# board1.net
KiCad netlist of a schematic drawn in EAGLE
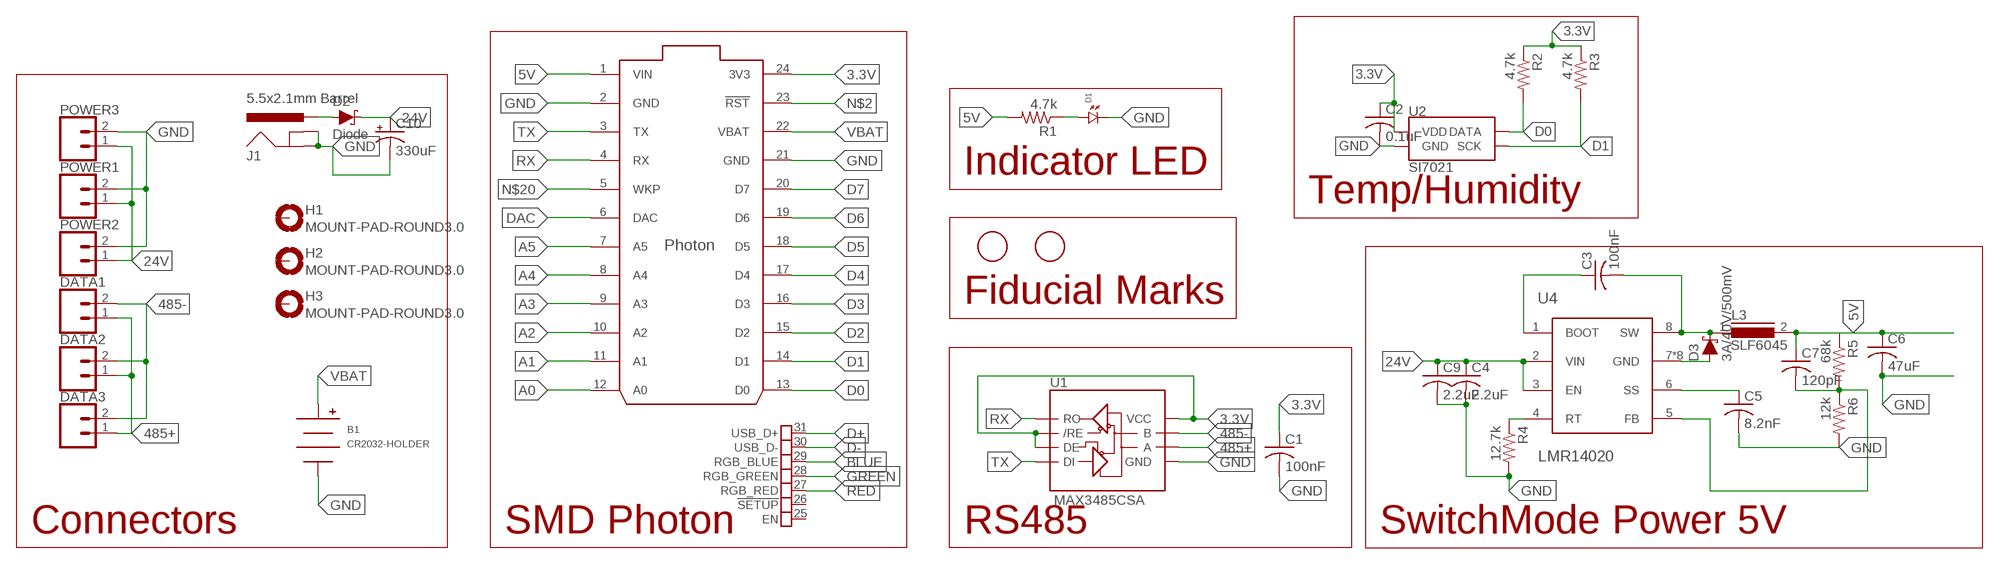
[diagram p0: schematic, sheet 1]

(export (version "E")
  (design (tool "Eeschema 10.0.6"))
  (components
    (comp (ref "B1")
      (value "CR2032-HOLDER")
      (footprint "eagle-import:CH28-2032LF")
      (libsource (lib "eagle-import") (part "CR2032-HOLDER"))
    )
    (comp (ref "C1")
      (value "100nF")
      (footprint "eagle-import:C0805")
      (libsource (lib "eagle-import") (part "C-USC0805"))
    )
    (comp (ref "C2")
      (value "0.1uF")
      (footprint "eagle-import:C0805")
      (libsource (lib "eagle-import") (part "C-USC0805"))
    )
    (comp (ref "C3")
      (value "100nF")
      (footprint "eagle-import:C0805")
      (libsource (lib "eagle-import") (part "C-USC0805"))
    )
    (comp (ref "C4")
      (value "2.2uF")
      (footprint "eagle-import:C0805")
      (libsource (lib "eagle-import") (part "C-USC0805"))
    )
    (comp (ref "C5")
      (value "8.2nF")
      (footprint "eagle-import:C0805")
      (libsource (lib "eagle-import") (part "C-USC0805"))
    )
    (comp (ref "C6")
      (value "47uF")
      (footprint "eagle-import:C0805")
      (libsource (lib "eagle-import") (part "C-USC0805"))
    )
    (comp (ref "C7")
      (value "120pF")
      (footprint "eagle-import:C0805")
      (libsource (lib "eagle-import") (part "C-USC0805"))
    )
    (comp (ref "C9")
      (value "2.2uF")
      (footprint "eagle-import:C0805")
      (libsource (lib "eagle-import") (part "C-USC0805"))
    )
    (comp (ref "C10")
      (value "330uF")
      (footprint "eagle-import:175TMP-0808")
      (libsource (lib "eagle-import") (part "CPOL-US175TMP-0808"))
    )
    (comp (ref "D1")
      (value "LED.0805")
      (footprint "eagle-import:0805.LED")
      (libsource (lib "eagle-import") (part "LED.0805"))
    )
    (comp (ref "D2")
      (value "Diode")
      (footprint "eagle-import:SMA-DIODE")
      (libsource (lib "eagle-import") (part "DIODE-SCHOTTKY-B340A"))
    )
    (comp (ref "D3")
      (value "3A/40V/500mV")
      (footprint "eagle-import:SMA-DIODE")
      (libsource (lib "eagle-import") (part "DIODE-SCHOTTKY-B340A"))
    )
    (comp (ref "DATA1")
      (value "CONN_025MM")
      (footprint "eagle-import:SCREWTERMINAL-5MM-2")
      (libsource (lib "eagle-import") (part "CONN_025MM"))
    )
    (comp (ref "DATA2")
      (value "CONN_025MM")
      (footprint "eagle-import:SCREWTERMINAL-5MM-2")
      (libsource (lib "eagle-import") (part "CONN_025MM"))
    )
    (comp (ref "DATA3")
      (value "CONN_025MM")
      (footprint "eagle-import:SCREWTERMINAL-5MM-2")
      (libsource (lib "eagle-import") (part "CONN_025MM"))
    )
    (comp (ref "FID1")
      (value "FIDUCIAL")
      (footprint "eagle-import:FIDUCIAL_1MM")
      (libsource (lib "eagle-import") (part "FIDUCIAL"))
    )
    (comp (ref "FID2")
      (value "FIDUCIAL")
      (footprint "eagle-import:FIDUCIAL_1MM")
      (libsource (lib "eagle-import") (part "FIDUCIAL"))
    )
    (comp (ref "H1")
      (value "MOUNT-PAD-ROUND3.0")
      (footprint "eagle-import:3,0-PAD")
      (libsource (lib "eagle-import") (part "MOUNT-PAD-ROUND3.0"))
    )
    (comp (ref "H2")
      (value "MOUNT-PAD-ROUND3.0")
      (footprint "eagle-import:3,0-PAD")
      (libsource (lib "eagle-import") (part "MOUNT-PAD-ROUND3.0"))
    )
    (comp (ref "H3")
      (value "MOUNT-PAD-ROUND3.0")
      (footprint "eagle-import:3,0-PAD")
      (libsource (lib "eagle-import") (part "MOUNT-PAD-ROUND3.0"))
    )
    (comp (ref "J1")
      (value "5.5x2.1mm Barrel")
      (footprint "eagle-import:POWER_JACK_SMD")
      (libsource (lib "eagle-import") (part "POWER_JACKSMD"))
    )
    (comp (ref "L3")
      (value "SLF6045")
      (footprint "eagle-import:SLF7045")
      (libsource (lib "eagle-import") (part "SLF7045"))
    )
    (comp (ref "POWER1")
      (value "CONN_025MM")
      (footprint "eagle-import:SCREWTERMINAL-5MM-2")
      (libsource (lib "eagle-import") (part "CONN_025MM"))
    )
    (comp (ref "POWER2")
      (value "CONN_025MM")
      (footprint "eagle-import:SCREWTERMINAL-5MM-2")
      (libsource (lib "eagle-import") (part "CONN_025MM"))
    )
    (comp (ref "POWER3")
      (value "CONN_025MM")
      (footprint "eagle-import:SCREWTERMINAL-5MM-2")
      (libsource (lib "eagle-import") (part "CONN_025MM"))
    )
    (comp (ref "R1")
      (value "4.7k")
      (footprint "eagle-import:R0805")
      (libsource (lib "eagle-import") (part "R-US_R0805"))
    )
    (comp (ref "R2")
      (value "4.7k")
      (footprint "eagle-import:R0805")
      (libsource (lib "eagle-import") (part "R-US_R0805"))
    )
    (comp (ref "R3")
      (value "4.7k")
      (footprint "eagle-import:R0805")
      (libsource (lib "eagle-import") (part "R-US_R0805"))
    )
    (comp (ref "R4")
      (value "12.7k")
      (footprint "eagle-import:R0805")
      (libsource (lib "eagle-import") (part "R-US_R0805"))
    )
    (comp (ref "R5")
      (value "68k")
      (footprint "eagle-import:R0805")
      (libsource (lib "eagle-import") (part "R-US_R0805"))
    )
    (comp (ref "R6")
      (value "12k")
      (footprint "eagle-import:R0805")
      (libsource (lib "eagle-import") (part "R-US_R0805"))
    )
    (comp (ref "U1")
      (value "MAX3485CSA")
      (footprint "eagle-import:SO08")
      (libsource (lib "eagle-import") (part "RS485SOIC"))
    )
    (comp (ref "U2")
      (value "SI7021")
      (footprint "eagle-import:DFN-6-3X3-SI7021")
      (libsource (lib "eagle-import") (part "SI7021"))
    )
    (comp (ref "U3")
      (value "PHOTON")
      (footprint "eagle-import:PHOTON_SMD")
      (libsource (lib "eagle-import") (part "PHOTON_SMD"))
    )
    (comp (ref "U4")
      (value "LMR14020")
      (footprint "eagle-import:SOIC8")
      (libsource (lib "eagle-import") (part "LMR14020"))
    )
  )
  (nets
    (net (code "1") (name "3.3V") (class "Default")
      (node (ref "C1") (pin "1") (pinfunction "1_1") (pintype "passive"))
      (node (ref "C2") (pin "1") (pinfunction "1_1") (pintype "passive"))
      (node (ref "R2") (pin "1") (pinfunction "1_1") (pintype "passive"))
      (node (ref "R3") (pin "1") (pinfunction "1_1") (pintype "passive"))
      (node (ref "U1") (pin "2") (pinfunction "/RE_2") (pintype "bidirectional"))
      (node (ref "U1") (pin "3") (pinfunction "DE_3") (pintype "bidirectional"))
      (node (ref "U1") (pin "8") (pinfunction "VCC_8") (pintype "bidirectional"))
      (node (ref "U2") (pin "VDD") (pinfunction "VDD_VDD") (pintype "power_in"))
      (node (ref "U3") (pin "24") (pinfunction "3V3_24") (pintype "power_in"))
    )
    (net (code "2") (name "5V") (class "Default")
      (node (ref "C6") (pin "1") (pinfunction "1_1") (pintype "passive"))
      (node (ref "C7") (pin "1") (pinfunction "1_1") (pintype "passive"))
      (node (ref "L3") (pin "2") (pinfunction "2_2") (pintype "passive"))
      (node (ref "R1") (pin "2") (pinfunction "2_2") (pintype "passive"))
      (node (ref "R5") (pin "1") (pinfunction "1_1") (pintype "passive"))
      (node (ref "U3") (pin "1") (pinfunction "VIN_1") (pintype "power_in"))
    )
    (net (code "3") (name "24V") (class "Default")
      (node (ref "C10") (pin "+") (pinfunction "+_+") (pintype "passive"))
      (node (ref "C4") (pin "1") (pinfunction "1_1") (pintype "passive"))
      (node (ref "C9") (pin "1") (pinfunction "1_1") (pintype "passive"))
      (node (ref "D2") (pin "C") (pinfunction "C_C") (pintype "passive"))
      (node (ref "POWER1") (pin "1") (pinfunction "1_1") (pintype "passive"))
      (node (ref "POWER2") (pin "1") (pinfunction "1_1") (pintype "passive"))
      (node (ref "POWER3") (pin "1") (pinfunction "1_1") (pintype "passive"))
      (node (ref "U4") (pin "2") (pinfunction "VIN_2") (pintype "bidirectional"))
      (node (ref "U4") (pin "3") (pinfunction "EN_3") (pintype "bidirectional"))
    )
    (net (code "4") (name "485+") (class "Default")
      (node (ref "DATA1") (pin "1") (pinfunction "1_1") (pintype "passive"))
      (node (ref "DATA2") (pin "1") (pinfunction "1_1") (pintype "passive"))
      (node (ref "DATA3") (pin "1") (pinfunction "1_1") (pintype "passive"))
      (node (ref "U1") (pin "6") (pinfunction "A_6") (pintype "bidirectional"))
    )
    (net (code "5") (name "485-") (class "Default")
      (node (ref "DATA1") (pin "2") (pinfunction "2_2") (pintype "passive"))
      (node (ref "DATA2") (pin "2") (pinfunction "2_2") (pintype "passive"))
      (node (ref "DATA3") (pin "2") (pinfunction "2_2") (pintype "passive"))
      (node (ref "U1") (pin "7") (pinfunction "B_7") (pintype "bidirectional"))
    )
    (net (code "6") (name "A0") (class "Default")
      (node (ref "U3") (pin "12") (pinfunction "A0_12") (pintype "bidirectional"))
    )
    (net (code "7") (name "A1") (class "Default")
      (node (ref "U3") (pin "11") (pinfunction "A1_11") (pintype "bidirectional"))
    )
    (net (code "8") (name "A2") (class "Default")
      (node (ref "U3") (pin "10") (pinfunction "A2_10") (pintype "bidirectional"))
    )
    (net (code "9") (name "A3") (class "Default")
      (node (ref "U3") (pin "9") (pinfunction "A3_9") (pintype "bidirectional"))
    )
    (net (code "10") (name "A4") (class "Default")
      (node (ref "U3") (pin "8") (pinfunction "A4_8") (pintype "bidirectional"))
    )
    (net (code "11") (name "A5") (class "Default")
      (node (ref "U3") (pin "7") (pinfunction "A5_7") (pintype "bidirectional"))
    )
    (net (code "12") (name "BLUE") (class "Default")
      (node (ref "U3") (pin "29") (pinfunction "RGB_BLUE_29") (pintype "bidirectional"))
    )
    (net (code "13") (name "D+") (class "Default")
      (node (ref "U3") (pin "31") (pinfunction "USB_D+_31") (pintype "bidirectional"))
    )
    (net (code "14") (name "D-") (class "Default")
      (node (ref "U3") (pin "30") (pinfunction "USB_D-_30") (pintype "bidirectional"))
    )
    (net (code "15") (name "D0") (class "Default")
      (node (ref "R2") (pin "2") (pinfunction "2_2") (pintype "passive"))
      (node (ref "U2") (pin "DATA") (pinfunction "DATA_DATA") (pintype "bidirectional"))
      (node (ref "U3") (pin "13") (pinfunction "D0_13") (pintype "bidirectional"))
    )
    (net (code "16") (name "D1") (class "Default")
      (node (ref "R3") (pin "2") (pinfunction "2_2") (pintype "passive"))
      (node (ref "U2") (pin "SCK") (pinfunction "SCK_SCK") (pintype "input"))
      (node (ref "U3") (pin "14") (pinfunction "D1_14") (pintype "bidirectional"))
    )
    (net (code "17") (name "D2") (class "Default")
      (node (ref "U3") (pin "15") (pinfunction "D2_15") (pintype "bidirectional"))
    )
    (net (code "18") (name "D3") (class "Default")
      (node (ref "U3") (pin "16") (pinfunction "D3_16") (pintype "bidirectional"))
    )
    (net (code "19") (name "D4") (class "Default")
      (node (ref "U3") (pin "17") (pinfunction "D4_17") (pintype "bidirectional"))
    )
    (net (code "20") (name "D5") (class "Default")
      (node (ref "U3") (pin "18") (pinfunction "D5_18") (pintype "bidirectional"))
    )
    (net (code "21") (name "D6") (class "Default")
      (node (ref "U3") (pin "19") (pinfunction "D6_19") (pintype "bidirectional"))
    )
    (net (code "22") (name "D7") (class "Default")
      (node (ref "U3") (pin "20") (pinfunction "D7_20") (pintype "bidirectional"))
    )
    (net (code "23") (name "DAC") (class "Default")
      (node (ref "U3") (pin "6") (pinfunction "DAC_6") (pintype "bidirectional"))
    )
    (net (code "24") (name "GND") (class "Default")
      (node (ref "B1") (pin "NEG") (pinfunction "NEG_NEG") (pintype "bidirectional"))
      (node (ref "C1") (pin "2") (pinfunction "2_2") (pintype "passive"))
      (node (ref "C10") (pin "-") (pinfunction "-_-") (pintype "passive"))
      (node (ref "C2") (pin "2") (pinfunction "2_2") (pintype "passive"))
      (node (ref "C4") (pin "2") (pinfunction "2_2") (pintype "passive"))
      (node (ref "C5") (pin "2") (pinfunction "2_2") (pintype "passive"))
      (node (ref "C6") (pin "2") (pinfunction "2_2") (pintype "passive"))
      (node (ref "C9") (pin "2") (pinfunction "2_2") (pintype "passive"))
      (node (ref "D1") (pin "P$2") (pinfunction "2_P$2") (pintype "bidirectional"))
      (node (ref "D3") (pin "A") (pinfunction "A_A") (pintype "passive"))
      (node (ref "J1") (pin "GND") (pinfunction "GNDBREAK_GND") (pintype "bidirectional"))
      (node (ref "J1") (pin "P$4") (pinfunction "GND_P$4") (pintype "bidirectional"))
      (node (ref "POWER1") (pin "2") (pinfunction "2_2") (pintype "passive"))
      (node (ref "POWER2") (pin "2") (pinfunction "2_2") (pintype "passive"))
      (node (ref "POWER3") (pin "2") (pinfunction "2_2") (pintype "passive"))
      (node (ref "R4") (pin "2") (pinfunction "2_2") (pintype "passive"))
      (node (ref "R6") (pin "2") (pinfunction "2_2") (pintype "passive"))
      (node (ref "U1") (pin "5") (pinfunction "GND_5") (pintype "bidirectional"))
      (node (ref "U2") (pin "GND") (pinfunction "GND_GND") (pintype "power_in"))
      (node (ref "U3") (pin "2") (pinfunction "GND_2") (pintype "power_in"))
      (node (ref "U3") (pin "21") (pinfunction "GND_21") (pintype "power_in"))
      (node (ref "U4") (pin "7") (pinfunction "GND_7") (pintype "bidirectional"))
      (node (ref "U4") (pin "GND@1") (pinfunction "GND_GND@1") (pintype "bidirectional"))
      (node (ref "U4") (pin "GND@2") (pinfunction "GND_GND@2") (pintype "bidirectional"))
      (node (ref "U4") (pin "GND@3") (pinfunction "GND_GND@3") (pintype "bidirectional"))
      (node (ref "U4") (pin "GND@4") (pinfunction "GND_GND@4") (pintype "bidirectional"))
      (node (ref "U4") (pin "GND@5") (pinfunction "GND_GND@5") (pintype "bidirectional"))
      (node (ref "U4") (pin "GND@6") (pinfunction "GND_GND@6") (pintype "bidirectional"))
      (node (ref "U4") (pin "GND@7") (pinfunction "GND_GND@7") (pintype "bidirectional"))
    )
    (net (code "25") (name "GREEN") (class "Default")
      (node (ref "U3") (pin "28") (pinfunction "RGB_GREEN_28") (pintype "bidirectional"))
    )
    (net (code "26") (name "N$2") (class "Default")
      (node (ref "U3") (pin "23") (pinfunction "~{RST}_23") (pintype "bidirectional"))
    )
    (net (code "27") (name "N$20") (class "Default")
      (node (ref "U3") (pin "5") (pinfunction "WKP_5") (pintype "bidirectional"))
    )
    (net (code "28") (name "Net-(D1-1)") (class "Default")
      (node (ref "D1") (pin "P$1") (pinfunction "1_P$1") (pintype "bidirectional"))
      (node (ref "R1") (pin "1") (pinfunction "1_1") (pintype "passive"))
    )
    (net (code "29") (name "Net-(J1-PWR)") (class "Default")
      (node (ref "D2") (pin "A") (pinfunction "A_A") (pintype "passive"))
      (node (ref "J1") (pin "VIN0") (pinfunction "PWR_VIN0") (pintype "bidirectional"))
    )
    (net (code "30") (name "Net-(U4-BOOT)") (class "Default")
      (node (ref "C3") (pin "1") (pinfunction "1_1") (pintype "passive"))
      (node (ref "U4") (pin "1") (pinfunction "BOOT_1") (pintype "bidirectional"))
    )
    (net (code "31") (name "Net-(U4-FB)") (class "Default")
      (node (ref "C7") (pin "2") (pinfunction "2_2") (pintype "passive"))
      (node (ref "R5") (pin "2") (pinfunction "2_2") (pintype "passive"))
      (node (ref "R6") (pin "1") (pinfunction "1_1") (pintype "passive"))
      (node (ref "U4") (pin "5") (pinfunction "FB_5") (pintype "bidirectional"))
    )
    (net (code "32") (name "Net-(U4-RT)") (class "Default")
      (node (ref "R4") (pin "1") (pinfunction "1_1") (pintype "passive"))
      (node (ref "U4") (pin "4") (pinfunction "RT_4") (pintype "bidirectional"))
    )
    (net (code "33") (name "Net-(U4-SS)") (class "Default")
      (node (ref "C5") (pin "1") (pinfunction "1_1") (pintype "passive"))
      (node (ref "U4") (pin "6") (pinfunction "SS_6") (pintype "bidirectional"))
    )
    (net (code "34") (name "Net-(U4-SW)") (class "Default")
      (node (ref "C3") (pin "2") (pinfunction "2_2") (pintype "passive"))
      (node (ref "D3") (pin "C") (pinfunction "C_C") (pintype "passive"))
      (node (ref "L3") (pin "1") (pinfunction "1_1") (pintype "passive"))
      (node (ref "U4") (pin "8") (pinfunction "SW_8") (pintype "bidirectional"))
    )
    (net (code "35") (name "RED") (class "Default")
      (node (ref "U3") (pin "27") (pinfunction "RGB_RED_27") (pintype "bidirectional"))
    )
    (net (code "36") (name "RX") (class "Default")
      (node (ref "U1") (pin "1") (pinfunction "RO_1") (pintype "bidirectional"))
      (node (ref "U3") (pin "4") (pinfunction "RX_4") (pintype "bidirectional"))
    )
    (net (code "37") (name "TX") (class "Default")
      (node (ref "U1") (pin "4") (pinfunction "DI_4") (pintype "bidirectional"))
      (node (ref "U3") (pin "3") (pinfunction "TX_3") (pintype "bidirectional"))
    )
    (net (code "38") (name "VBAT") (class "Default")
      (node (ref "B1") (pin "POS") (pinfunction "POS_POS") (pintype "bidirectional"))
      (node (ref "U3") (pin "22") (pinfunction "VBAT_22") (pintype "power_in"))
    )
    (net (code "39") (name "unconnected-(H1-MOUNT-PadB3,0)") (class "Default")
      (node (ref "H1") (pin "B3,0") (pinfunction "MOUNT_B3,0") (pintype "passive"))
    )
    (net (code "40") (name "unconnected-(H2-MOUNT-PadB3,0)") (class "Default")
      (node (ref "H2") (pin "B3,0") (pinfunction "MOUNT_B3,0") (pintype "passive"))
    )
    (net (code "41") (name "unconnected-(H3-MOUNT-PadB3,0)") (class "Default")
      (node (ref "H3") (pin "B3,0") (pinfunction "MOUNT_B3,0") (pintype "passive"))
    )
    (net (code "42") (name "unconnected-(U3B-EN-Pad25)") (class "Default")
      (node (ref "U3") (pin "25") (pinfunction "EN_25") (pintype "bidirectional"))
    )
    (net (code "43") (name "unconnected-(U3B-~{SETUP}-Pad26)") (class "Default")
      (node (ref "U3") (pin "26") (pinfunction "~{SETUP}_26") (pintype "bidirectional"))
    )
  )
)
